# 100068622_data_switches.net
KiCad netlist of a schematic drawn in Altium Designer
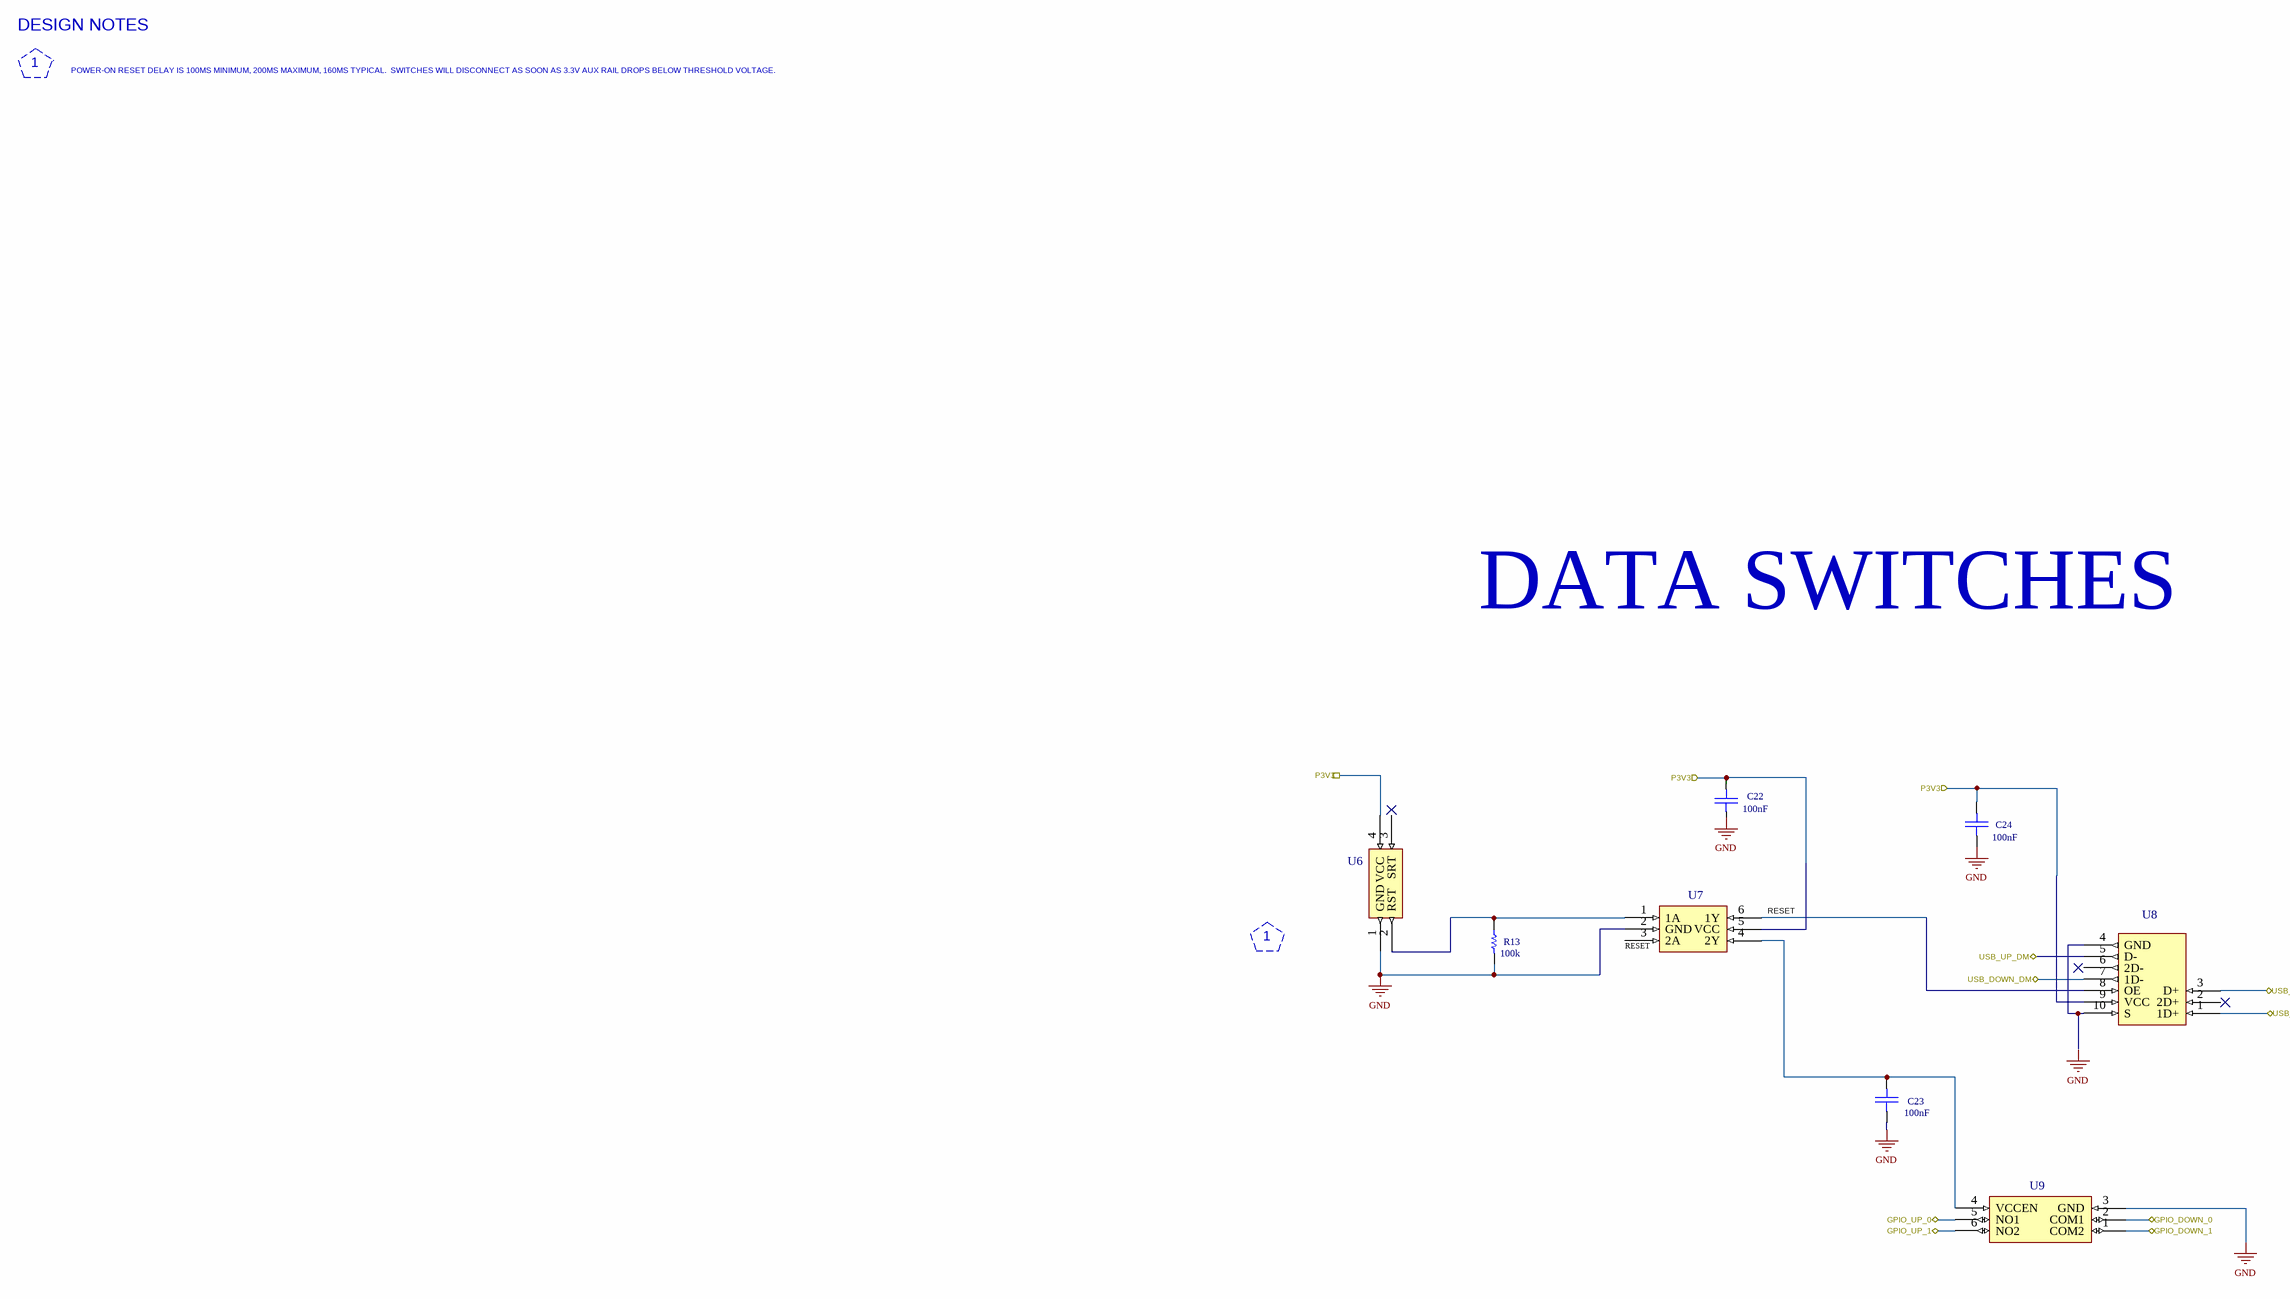
[diagram p0: 100068622_data_switches.SchDoc]

(export (version "E")
  (design (tool "Eeschema 10.0.6"))
  (components
    (comp (ref "C22")
      (value "100nF")
      (footprint "CAP-0402-A")
      (description "CAP 0402 0.1UF 50V 10% X5R")
      (fields (field (name "TOLERANCE") "10%"))
      (libsource (lib "Picatinny Server") (part "Capacitor - Non-Polarized"))
    )
    (comp (ref "C23")
      (value "100nF")
      (footprint "CAP-0402-A")
      (description "CAP 0402 0.1UF 50V 10% X5R")
      (fields (field (name "TOLERANCE") "10%"))
      (libsource (lib "Picatinny Server") (part "Capacitor - Non-Polarized"))
    )
    (comp (ref "C24")
      (value "100nF")
      (footprint "CAP-0402-A")
      (description "CAP 0402 0.1UF 50V 10% X5R")
      (fields (field (name "TOLERANCE") "10%"))
      (libsource (lib "Picatinny Server") (part "Capacitor - Non-Polarized"))
    )
    (comp (ref "R13")
      (value "100k")
      (footprint "RES-0402-C")
      (description "Res 0402 100K 1/10W 1% Thick Flim")
      (fields (field (name "TOLERANCE") "1%"))
      (libsource (lib "Picatinny Server") (part "Resistor"))
    )
    (comp (ref "U6")
      (value "MAX821UUS+T")
      (footprint "IC-SOT143-4-A")
      (description "4-Pin, µP Voltage Monitors with Pin-Selectable Power-On Reset Timeout Delay")
      (libsource (lib "Picatinny Server") (part "MAX821UUS+T"))
    )
    (comp (ref "U7")
      (value "SN74AUP2G04DRYR")
      (footprint "IC-SON6-A")
      (description "IC INVERTER 2CH 2-INP 6SON Inverter IC 2 Channel 6-SON (1.45x1)")
      (libsource (lib "Picatinny Server") (part "SN74AUP2G04DRYR"))
    )
    (comp (ref "U8")
      (value "TC7USB40MU")
      (footprint "IC-UQFN10-A")
      (description "USB Interface, 1: 2 Multiplexer/Demultiplexer Switch, USB 2.0, 2.3 V, 4.3 V, UQFN-B, 10 Pins")
      (libsource (lib "Picatinny Server") (part "TC7USB40MU"))
    )
    (comp (ref "U9")
      (value "MAX20336AEFT+T")
      (footprint "IC-FC2QFN-A")
      (description "Industry's Smallest DPST Can Switch ±5.5V Signals with a Single VCC as Low as 1.6V")
      (libsource (lib "Picatinny Server") (part "MAX20336AEFT+T"))
    )
  )
  (nets
    (net (code "1") (name "/GPIO_DOWN_0") (class "Default")
      (node (ref "U9") (pin "2") (pinfunction "COM1_2") (pintype "bidirectional"))
    )
    (net (code "2") (name "/GPIO_DOWN_1") (class "Default")
      (node (ref "U9") (pin "1") (pinfunction "COM2_1") (pintype "bidirectional"))
    )
    (net (code "3") (name "/GPIO_UP_0") (class "Default")
      (node (ref "U9") (pin "5") (pinfunction "NO1_5") (pintype "bidirectional"))
    )
    (net (code "4") (name "/GPIO_UP_1") (class "Default")
      (node (ref "U9") (pin "6") (pinfunction "NO2_6") (pintype "bidirectional"))
    )
    (net (code "5") (name "/P3V3") (class "Default")
      (node (ref "C22") (pin "1") (pinfunction "1_1") (pintype "passive"))
      (node (ref "C24") (pin "2") (pinfunction "2_2") (pintype "passive"))
      (node (ref "U7") (pin "5") (pinfunction "VCC_5") (pintype "input"))
      (node (ref "U8") (pin "9") (pinfunction "VCC_9") (pintype "input"))
    )
    (net (code "7") (name "/USB_DOWN_DM") (class "Default")
      (node (ref "U8") (pin "7") (pinfunction "1D-_7") (pintype "output"))
    )
    (net (code "8") (name "/USB_DOWN_DP") (class "Default")
      (node (ref "U8") (pin "1") (pinfunction "1D+_1") (pintype "input"))
    )
    (net (code "10") (name "/USB_UP_DP") (class "Default")
      (node (ref "U8") (pin "3") (pinfunction "D+_3") (pintype "input"))
    )
    (net (code "11") (name "GND") (class "Default")
      (node (ref "C23") (pin "1") (pinfunction "1_1") (pintype "passive"))
      (node (ref "C24") (pin "1") (pinfunction "1_1") (pintype "passive"))
      (node (ref "R13") (pin "1") (pinfunction "1_1") (pintype "passive"))
      (node (ref "U6") (pin "1") (pinfunction "GND_1") (pintype "output"))
      (node (ref "U7") (pin "2") (pinfunction "GND_2") (pintype "input"))
      (node (ref "U9") (pin "3") (pinfunction "GND_3") (pintype "input"))
    )
    (net (code "12") (name "Net-(U6-RST)") (class "Default")
      (node (ref "R13") (pin "2") (pinfunction "2_2") (pintype "passive"))
      (node (ref "U6") (pin "2") (pinfunction "RST_2") (pintype "output"))
      (node (ref "U7") (pin "1") (pinfunction "1A_1") (pintype "input"))
    )
    (net (code "13") (name "Net-(U7-1Y)") (class "Default")
      (node (ref "U7") (pin "6") (pinfunction "1Y_6") (pintype "input"))
      (node (ref "U8") (pin "8") (pinfunction "OE_8") (pintype "input"))
    )
    (net (code "14") (name "Net-(U7-2Y)") (class "Default")
      (node (ref "C23") (pin "2") (pinfunction "2_2") (pintype "passive"))
      (node (ref "U7") (pin "4") (pinfunction "2Y_4") (pintype "input"))
      (node (ref "U9") (pin "4") (pinfunction "VCCEN_4") (pintype "input"))
    )
    (net (code "15") (name "Net-(U8-GND)") (class "Default")
      (node (ref "U8") (pin "10") (pinfunction "S_10") (pintype "input"))
      (node (ref "U8") (pin "4") (pinfunction "GND_4") (pintype "output"))
    )
    (net (code "16") (name "unconnected-(C22-Pad2)") (class "Default")
      (node (ref "C22") (pin "2") (pinfunction "2_2") (pintype "passive"))
    )
    (net (code "17") (name "unconnected-(U6-SRT-Pad3)") (class "Default")
      (node (ref "U6") (pin "3") (pinfunction "SRT_3") (pintype "input"))
    )
    (net (code "18") (name "unconnected-(U6-VCC-Pad4)") (class "Default")
      (node (ref "U6") (pin "4") (pinfunction "VCC_4") (pintype "input"))
    )
    (net (code "19") (name "unconnected-(U7-2A-Pad3)") (class "Default")
      (node (ref "U7") (pin "3") (pinfunction "2A_3") (pintype "input"))
    )
    (net (code "20") (name "unconnected-(U8-2D+-Pad2)") (class "Default")
      (node (ref "U8") (pin "2") (pinfunction "2D+_2") (pintype "input"))
    )
    (net (code "21") (name "unconnected-(U8-2D--Pad6)") (class "Default")
      (node (ref "U8") (pin "6") (pinfunction "2D-_6") (pintype "output"))
    )
    (net (code "22") (name "unconnected-(U8-D--Pad5)") (class "Default")
      (node (ref "U8") (pin "5") (pinfunction "D-_5") (pintype "output"))
    )
  )
)
